# LowSpeedSlots_x8.net
KiCad netlist of a schematic drawn in Altium Designer
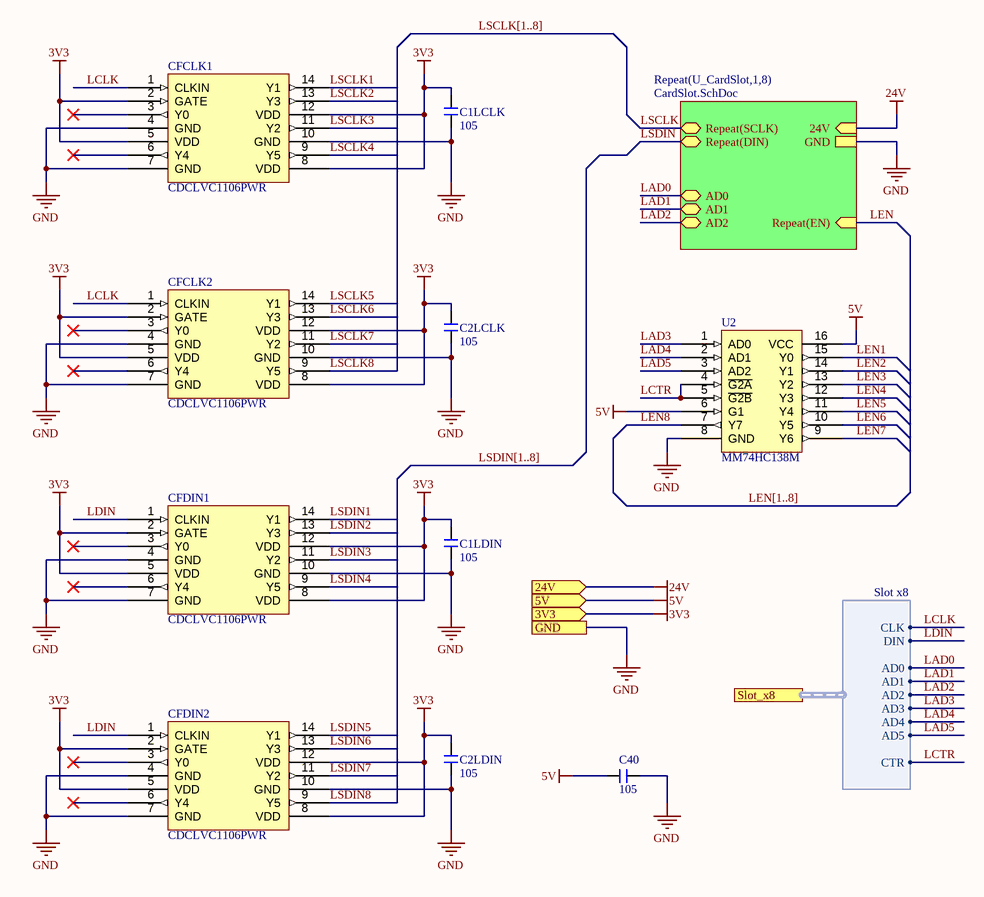
[diagram p0: LowSpeedSlots_x8.SchDoc]

(export (version "E")
  (design (tool "Eeschema 10.0.6"))
  (components
    (comp (ref "C1LCLK")
      (value "105")
      (footprint "C 0603_L")
      (description "贴片电容")
      (libsource (lib "0.1 - 电阻-电容-电感") (part "C"))
    )
    (comp (ref "C1LDIN")
      (value "105")
      (footprint "C 0603_L")
      (description "贴片电容")
      (libsource (lib "0.1 - 电阻-电容-电感") (part "C"))
    )
    (comp (ref "C2LCLK")
      (value "105")
      (footprint "C 0603_L")
      (description "贴片电容")
      (libsource (lib "0.1 - 电阻-电容-电感") (part "C"))
    )
    (comp (ref "C2LDIN")
      (value "105")
      (footprint "C 0603_L")
      (description "贴片电容")
      (libsource (lib "0.1 - 电阻-电容-电感") (part "C"))
    )
    (comp (ref "C40")
      (value "105")
      (footprint "C 0603_L")
      (description "贴片电容")
      (libsource (lib "0.1 - 电阻-电容-电感") (part "C"))
    )
    (comp (ref "CFCLK1")
      (value "CDCLVC1106PWR")
      (footprint "TSSOP14_L")
      (description "1:6 Clock Fan-out Buffer")
      (libsource (lib "CustomizedComponents") (part "CDCLVC1106PWR"))
    )
    (comp (ref "CFCLK2")
      (value "CDCLVC1106PWR")
      (footprint "TSSOP14_L")
      (description "1:6 Clock Fan-out Buffer")
      (libsource (lib "CustomizedComponents") (part "CDCLVC1106PWR"))
    )
    (comp (ref "CFDIN1")
      (value "CDCLVC1106PWR")
      (footprint "TSSOP14_L")
      (description "1:6 Clock Fan-out Buffer")
      (libsource (lib "CustomizedComponents") (part "CDCLVC1106PWR"))
    )
    (comp (ref "CFDIN2")
      (value "CDCLVC1106PWR")
      (footprint "TSSOP14_L")
      (description "1:6 Clock Fan-out Buffer")
      (libsource (lib "CustomizedComponents") (part "CDCLVC1106PWR"))
    )
    (comp (ref "U2")
      (value "MM74HC138M")
      (footprint "SO16NB")
      (description "3-to-8 Decoder")
      (libsource (lib "CustomizedComponents") (part "MM74HC138M"))
    )
  )
  (nets
    (net (code "6") (name "/LAD3") (class "Default")
      (node (ref "U2") (pin "1") (pinfunction "AD0_1") (pintype "input"))
    )
    (net (code "7") (name "/LAD4") (class "Default")
      (node (ref "U2") (pin "2") (pinfunction "AD1_2") (pintype "input"))
    )
    (net (code "8") (name "/LAD5") (class "Default")
      (node (ref "U2") (pin "3") (pinfunction "AD2_3") (pintype "input"))
    )
    (net (code "9") (name "/LCLK") (class "Default")
      (node (ref "CFCLK1") (pin "1") (pinfunction "CLKIN_1") (pintype "input"))
      (node (ref "CFCLK2") (pin "1") (pinfunction "CLKIN_1") (pintype "input"))
    )
    (net (code "10") (name "/LCTR") (class "Default")
      (node (ref "U2") (pin "4") (pinfunction "G2A_4") (pintype "input"))
      (node (ref "U2") (pin "5") (pinfunction "G2B_5") (pintype "input"))
    )
    (net (code "11") (name "/LDIN") (class "Default")
      (node (ref "CFDIN1") (pin "1") (pinfunction "CLKIN_1") (pintype "input"))
      (node (ref "CFDIN2") (pin "1") (pinfunction "CLKIN_1") (pintype "input"))
    )
    (net (code "13") (name "/LEN1") (class "Default")
      (node (ref "U2") (pin "15") (pinfunction "Y0_15") (pintype "output"))
    )
    (net (code "14") (name "/LEN2") (class "Default")
      (node (ref "U2") (pin "14") (pinfunction "Y1_14") (pintype "output"))
    )
    (net (code "15") (name "/LEN3") (class "Default")
      (node (ref "U2") (pin "13") (pinfunction "Y2_13") (pintype "output"))
    )
    (net (code "16") (name "/LEN4") (class "Default")
      (node (ref "U2") (pin "12") (pinfunction "Y3_12") (pintype "output"))
    )
    (net (code "17") (name "/LEN5") (class "Default")
      (node (ref "U2") (pin "11") (pinfunction "Y4_11") (pintype "output"))
    )
    (net (code "18") (name "/LEN6") (class "Default")
      (node (ref "U2") (pin "10") (pinfunction "Y5_10") (pintype "output"))
    )
    (net (code "19") (name "/LEN7") (class "Default")
      (node (ref "U2") (pin "9") (pinfunction "Y6_9") (pintype "output"))
    )
    (net (code "20") (name "/LEN8") (class "Default")
      (node (ref "U2") (pin "7") (pinfunction "Y7_7") (pintype "output"))
    )
    (net (code "23") (name "/LSCLK1") (class "Default")
      (node (ref "CFCLK1") (pin "14") (pinfunction "Y1_14") (pintype "output"))
    )
    (net (code "24") (name "/LSCLK2") (class "Default")
      (node (ref "CFCLK1") (pin "13") (pinfunction "Y3_13") (pintype "output"))
    )
    (net (code "25") (name "/LSCLK3") (class "Default")
      (node (ref "CFCLK1") (pin "11") (pinfunction "Y2_11") (pintype "output"))
    )
    (net (code "26") (name "/LSCLK4") (class "Default")
      (node (ref "CFCLK1") (pin "9") (pinfunction "Y5_9") (pintype "output"))
    )
    (net (code "27") (name "/LSCLK5") (class "Default")
      (node (ref "CFCLK2") (pin "14") (pinfunction "Y1_14") (pintype "output"))
    )
    (net (code "28") (name "/LSCLK6") (class "Default")
      (node (ref "CFCLK2") (pin "13") (pinfunction "Y3_13") (pintype "output"))
    )
    (net (code "29") (name "/LSCLK7") (class "Default")
      (node (ref "CFCLK2") (pin "11") (pinfunction "Y2_11") (pintype "output"))
    )
    (net (code "30") (name "/LSCLK8") (class "Default")
      (node (ref "CFCLK2") (pin "9") (pinfunction "Y5_9") (pintype "output"))
    )
    (net (code "33") (name "/LSDIN1") (class "Default")
      (node (ref "CFDIN1") (pin "14") (pinfunction "Y1_14") (pintype "output"))
    )
    (net (code "34") (name "/LSDIN2") (class "Default")
      (node (ref "CFDIN1") (pin "13") (pinfunction "Y3_13") (pintype "output"))
    )
    (net (code "35") (name "/LSDIN3") (class "Default")
      (node (ref "CFDIN1") (pin "11") (pinfunction "Y2_11") (pintype "output"))
    )
    (net (code "36") (name "/LSDIN4") (class "Default")
      (node (ref "CFDIN1") (pin "9") (pinfunction "Y5_9") (pintype "output"))
    )
    (net (code "37") (name "/LSDIN5") (class "Default")
      (node (ref "CFDIN2") (pin "14") (pinfunction "Y1_14") (pintype "output"))
    )
    (net (code "38") (name "/LSDIN6") (class "Default")
      (node (ref "CFDIN2") (pin "13") (pinfunction "Y3_13") (pintype "output"))
    )
    (net (code "39") (name "/LSDIN7") (class "Default")
      (node (ref "CFDIN2") (pin "11") (pinfunction "Y2_11") (pintype "output"))
    )
    (net (code "40") (name "/LSDIN8") (class "Default")
      (node (ref "CFDIN2") (pin "9") (pinfunction "Y5_9") (pintype "output"))
    )
    (net (code "43") (name "3V3") (class "Default")
      (node (ref "C1LCLK") (pin "2") (pinfunction "2_2") (pintype "passive"))
      (node (ref "C1LDIN") (pin "2") (pinfunction "2_2") (pintype "passive"))
      (node (ref "C2LCLK") (pin "2") (pinfunction "2_2") (pintype "passive"))
      (node (ref "C2LDIN") (pin "2") (pinfunction "2_2") (pintype "passive"))
      (node (ref "CFCLK1") (pin "12") (pinfunction "VDD_12") (pintype "power_in"))
      (node (ref "CFCLK1") (pin "2") (pinfunction "GATE_2") (pintype "input"))
      (node (ref "CFCLK1") (pin "5") (pinfunction "VDD_5") (pintype "power_in"))
      (node (ref "CFCLK1") (pin "8") (pinfunction "VDD_8") (pintype "power_in"))
      (node (ref "CFCLK2") (pin "12") (pinfunction "VDD_12") (pintype "power_in"))
      (node (ref "CFCLK2") (pin "2") (pinfunction "GATE_2") (pintype "input"))
      (node (ref "CFCLK2") (pin "5") (pinfunction "VDD_5") (pintype "power_in"))
      (node (ref "CFCLK2") (pin "8") (pinfunction "VDD_8") (pintype "power_in"))
      (node (ref "CFDIN1") (pin "12") (pinfunction "VDD_12") (pintype "power_in"))
      (node (ref "CFDIN1") (pin "2") (pinfunction "GATE_2") (pintype "input"))
      (node (ref "CFDIN1") (pin "5") (pinfunction "VDD_5") (pintype "power_in"))
      (node (ref "CFDIN1") (pin "8") (pinfunction "VDD_8") (pintype "power_in"))
      (node (ref "CFDIN2") (pin "12") (pinfunction "VDD_12") (pintype "power_in"))
      (node (ref "CFDIN2") (pin "2") (pinfunction "GATE_2") (pintype "input"))
      (node (ref "CFDIN2") (pin "5") (pinfunction "VDD_5") (pintype "power_in"))
      (node (ref "CFDIN2") (pin "8") (pinfunction "VDD_8") (pintype "power_in"))
    )
    (net (code "44") (name "5V") (class "Default")
      (node (ref "C40") (pin "2") (pinfunction "2_2") (pintype "passive"))
      (node (ref "U2") (pin "16") (pinfunction "VCC_16") (pintype "power_in"))
      (node (ref "U2") (pin "6") (pinfunction "G1_6") (pintype "input"))
    )
    (net (code "46") (name "GND") (class "Default")
      (node (ref "C1LCLK") (pin "1") (pinfunction "1_1") (pintype "passive"))
      (node (ref "C1LDIN") (pin "1") (pinfunction "1_1") (pintype "passive"))
      (node (ref "C2LCLK") (pin "1") (pinfunction "1_1") (pintype "passive"))
      (node (ref "C2LDIN") (pin "1") (pinfunction "1_1") (pintype "passive"))
      (node (ref "C40") (pin "1") (pinfunction "1_1") (pintype "passive"))
      (node (ref "CFCLK1") (pin "10") (pinfunction "GND_10") (pintype "power_in"))
      (node (ref "CFCLK1") (pin "4") (pinfunction "GND_4") (pintype "power_in"))
      (node (ref "CFCLK1") (pin "7") (pinfunction "GND_7") (pintype "power_in"))
      (node (ref "CFCLK2") (pin "10") (pinfunction "GND_10") (pintype "power_in"))
      (node (ref "CFCLK2") (pin "4") (pinfunction "GND_4") (pintype "power_in"))
      (node (ref "CFCLK2") (pin "7") (pinfunction "GND_7") (pintype "power_in"))
      (node (ref "CFDIN1") (pin "10") (pinfunction "GND_10") (pintype "power_in"))
      (node (ref "CFDIN1") (pin "4") (pinfunction "GND_4") (pintype "power_in"))
      (node (ref "CFDIN1") (pin "7") (pinfunction "GND_7") (pintype "power_in"))
      (node (ref "CFDIN2") (pin "10") (pinfunction "GND_10") (pintype "power_in"))
      (node (ref "CFDIN2") (pin "4") (pinfunction "GND_4") (pintype "power_in"))
      (node (ref "CFDIN2") (pin "7") (pinfunction "GND_7") (pintype "power_in"))
      (node (ref "U2") (pin "8") (pinfunction "GND_8") (pintype "power_in"))
    )
    (net (code "47") (name "unconnected-(CFCLK1-Y0-Pad3)") (class "Default")
      (node (ref "CFCLK1") (pin "3") (pinfunction "Y0_3") (pintype "output+no_connect"))
    )
    (net (code "48") (name "unconnected-(CFCLK1-Y4-Pad6)") (class "Default")
      (node (ref "CFCLK1") (pin "6") (pinfunction "Y4_6") (pintype "output+no_connect"))
    )
    (net (code "49") (name "unconnected-(CFCLK2-Y0-Pad3)") (class "Default")
      (node (ref "CFCLK2") (pin "3") (pinfunction "Y0_3") (pintype "output+no_connect"))
    )
    (net (code "50") (name "unconnected-(CFCLK2-Y4-Pad6)") (class "Default")
      (node (ref "CFCLK2") (pin "6") (pinfunction "Y4_6") (pintype "output+no_connect"))
    )
    (net (code "51") (name "unconnected-(CFDIN1-Y0-Pad3)") (class "Default")
      (node (ref "CFDIN1") (pin "3") (pinfunction "Y0_3") (pintype "output+no_connect"))
    )
    (net (code "52") (name "unconnected-(CFDIN1-Y4-Pad6)") (class "Default")
      (node (ref "CFDIN1") (pin "6") (pinfunction "Y4_6") (pintype "output+no_connect"))
    )
    (net (code "53") (name "unconnected-(CFDIN2-Y0-Pad3)") (class "Default")
      (node (ref "CFDIN2") (pin "3") (pinfunction "Y0_3") (pintype "output+no_connect"))
    )
    (net (code "54") (name "unconnected-(CFDIN2-Y4-Pad6)") (class "Default")
      (node (ref "CFDIN2") (pin "6") (pinfunction "Y4_6") (pintype "output+no_connect"))
    )
  )
)
